# Teensy_Reactor.net
KiCad netlist of a schematic drawn in EAGLE
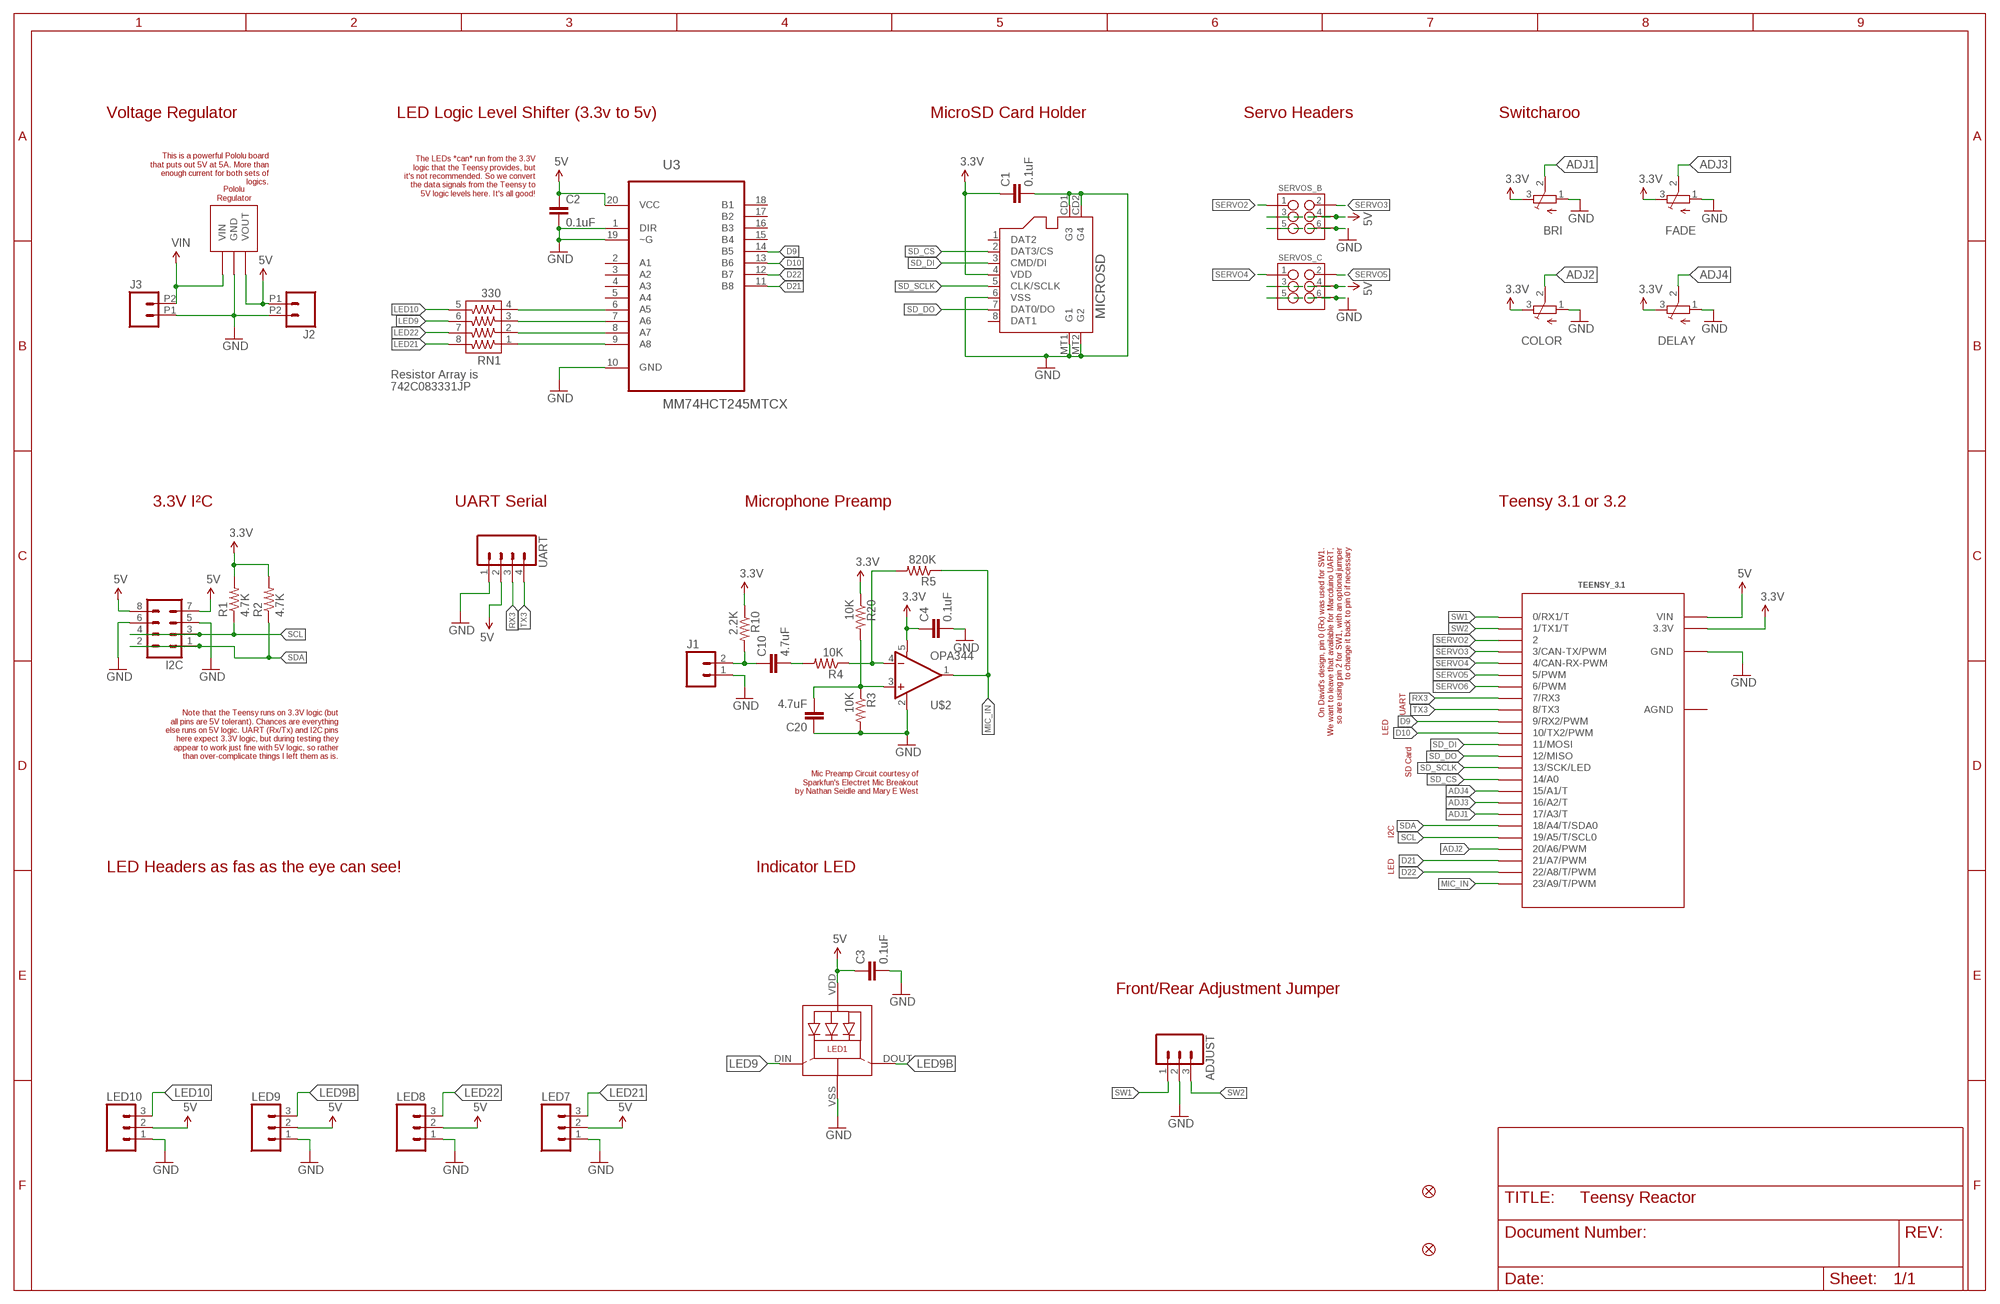
[diagram p0: schematic, sheet 1]

(export (version "E")
  (design (tool "Eeschema 10.0.6"))
  (components
    (comp (ref "ADJUST")
      (value "M03PTH")
      (footprint "eagle-import:1X03")
      (libsource (lib "eagle-import") (part "M03PTH"))
    )
    (comp (ref "BRI")
      (value "TRIMPOTEVM3V")
      (footprint "eagle-import:EVM3V")
      (libsource (lib "eagle-import") (part "TRIMPOTEVM3V"))
    )
    (comp (ref "C1")
      (value "0.1uF")
      (footprint "eagle-import:0603-CAP")
      (libsource (lib "eagle-import") (part "2.2UF-10V-20%(0603)"))
    )
    (comp (ref "C2")
      (value "0.1uF")
      (footprint "eagle-import:0603-CAP")
      (libsource (lib "eagle-import") (part "2.2UF-10V-20%(0603)"))
    )
    (comp (ref "C3")
      (value "0.1uF")
      (footprint "eagle-import:0603-CAP")
      (libsource (lib "eagle-import") (part "2.2UF-10V-20%(0603)"))
    )
    (comp (ref "C4")
      (value "0.1uF")
      (footprint "eagle-import:0603-CAP")
      (libsource (lib "eagle-import") (part "2.2UF-10V-20%(0603)"))
    )
    (comp (ref "C10")
      (value "4.7uF")
      (footprint "eagle-import:0603-CAP")
      (libsource (lib "eagle-import") (part "2.2UF-10V-20%(0603)"))
    )
    (comp (ref "C20")
      (value "4.7uF")
      (footprint "eagle-import:0603-CAP")
      (libsource (lib "eagle-import") (part "2.2UF-10V-20%(0603)"))
    )
    (comp (ref "COLOR")
      (value "TRIMPOTEVM3V")
      (footprint "eagle-import:EVM3V")
      (libsource (lib "eagle-import") (part "TRIMPOTEVM3V"))
    )
    (comp (ref "DELAY")
      (value "TRIMPOTEVM3V")
      (footprint "eagle-import:EVM3V")
      (libsource (lib "eagle-import") (part "TRIMPOTEVM3V"))
    )
    (comp (ref "FADE")
      (value "TRIMPOTEVM3V")
      (footprint "eagle-import:EVM3V")
      (libsource (lib "eagle-import") (part "TRIMPOTEVM3V"))
    )
    (comp (ref "FID1")
      (value "FIDUCIAL1X2")
      (footprint "eagle-import:FIDUCIAL-1X2")
      (libsource (lib "eagle-import") (part "FIDUCIAL1X2"))
    )
    (comp (ref "FID2")
      (value "FIDUCIAL1X2")
      (footprint "eagle-import:FIDUCIAL-1X2")
      (libsource (lib "eagle-import") (part "FIDUCIAL1X2"))
    )
    (comp (ref "I2C")
      (value "M04X2")
      (footprint "eagle-import:2X4")
      (libsource (lib "eagle-import") (part "M04X2"))
    )
    (comp (ref "J1")
      (value "M02PTH")
      (footprint "eagle-import:1X02")
      (libsource (lib "eagle-import") (part "M02PTH"))
    )
    (comp (ref "J2")
      (value "M022.54MM_SCREWTERM")
      (footprint "eagle-import:1X02_2.54_SCREWTERM")
      (libsource (lib "eagle-import") (part "M022.54MM_SCREWTERM"))
    )
    (comp (ref "J3")
      (value "M022.54MM_SCREWTERM")
      (footprint "eagle-import:1X02_2.54_SCREWTERM")
      (libsource (lib "eagle-import") (part "M022.54MM_SCREWTERM"))
    )
    (comp (ref "LED1")
      (value "WS2812BSK6812MINI")
      (footprint "eagle-import:SK6812MINI")
      (libsource (lib "eagle-import") (part "WS2812BSK6812MINI"))
    )
    (comp (ref "LED7")
      (value "M03PTH")
      (footprint "eagle-import:1X03")
      (libsource (lib "eagle-import") (part "M03PTH"))
    )
    (comp (ref "LED8")
      (value "M03PTH")
      (footprint "eagle-import:1X03")
      (libsource (lib "eagle-import") (part "M03PTH"))
    )
    (comp (ref "LED9")
      (value "M03PTH")
      (footprint "eagle-import:1X03")
      (libsource (lib "eagle-import") (part "M03PTH"))
    )
    (comp (ref "LED10")
      (value "M03PTH")
      (footprint "eagle-import:1X03")
      (libsource (lib "eagle-import") (part "M03PTH"))
    )
    (comp (ref "MICROSD")
      (value "MICROSD")
      (footprint "eagle-import:MICROSD_SMALL")
      (libsource (lib "eagle-import") (part "MICROSD"))
    )
    (comp (ref "R1")
      (value "4.7K")
      (footprint "eagle-import:0603-RES")
      (libsource (lib "eagle-import") (part "RESISTOR0603-RES"))
    )
    (comp (ref "R2")
      (value "4.7K")
      (footprint "eagle-import:0603-RES")
      (libsource (lib "eagle-import") (part "RESISTOR0603-RES"))
    )
    (comp (ref "R3")
      (value "10K")
      (footprint "eagle-import:0603-RES")
      (libsource (lib "eagle-import") (part "RESISTOR0603-RES"))
    )
    (comp (ref "R4")
      (value "10K")
      (footprint "eagle-import:0603-RES")
      (libsource (lib "eagle-import") (part "RESISTOR0603-RES"))
    )
    (comp (ref "R5")
      (value "820K")
      (footprint "eagle-import:0603-RES")
      (libsource (lib "eagle-import") (part "RESISTOR0603-RES"))
    )
    (comp (ref "R10")
      (value "2.2K")
      (footprint "eagle-import:0603-RES")
      (libsource (lib "eagle-import") (part "RESISTOR0603-RES"))
    )
    (comp (ref "R20")
      (value "10K")
      (footprint "eagle-import:0603-RES")
      (libsource (lib "eagle-import") (part "RESISTOR0603-RES"))
    )
    (comp (ref "RN1")
      (value "330")
      (footprint "eagle-import:742-8NS")
      (libsource (lib "eagle-import") (part "742-8NS"))
    )
    (comp (ref "SERVOS_B")
      (value "M03X22X3_SILK_MALE_PTH")
      (footprint "eagle-import:2X3")
      (libsource (lib "eagle-import") (part "M03X22X3_SILK_MALE_PTH"))
    )
    (comp (ref "SERVOS_C")
      (value "M03X22X3_SILK_MALE_PTH")
      (footprint "eagle-import:2X3")
      (libsource (lib "eagle-import") (part "M03X22X3_SILK_MALE_PTH"))
    )
    (comp (ref "TEENSY_3.1")
      (value "TEENSY_3.1_SOME_PINS")
      (footprint "eagle-import:TEENSY3-SOME_PINS")
      (libsource (lib "eagle-import") (part "TEENSY_3.1_SOME_PINS"))
    )
    (comp (ref "U$1")
      (value "POLOLU_REGD24V50FS_NO_HOLES")
      (footprint "eagle-import:D24V50F5_NO_HOLES")
      (libsource (lib "eagle-import") (part "POLOLU_REGD24V50FS_NO_HOLES"))
    )
    (comp (ref "U$2")
      (value "OPA344")
      (footprint "eagle-import:SOT23-5")
      (libsource (lib "eagle-import") (part "OPA344"))
    )
    (comp (ref "U3")
      (value "MM74HCT245MTCX")
      (footprint "eagle-import:SOP65P640X120-20N")
      (libsource (lib "eagle-import") (part "MM74HCT245MTCX"))
    )
    (comp (ref "UART")
      (value "M04PTH")
      (footprint "eagle-import:1X04")
      (libsource (lib "eagle-import") (part "M04PTH"))
    )
  )
  (nets
    (net (code "1") (name "/AGND") (class "Default")
      (node (ref "TEENSY_3.1") (pin "AGND") (pinfunction "AGND_AGND") (pintype "power_in"))
    )
    (net (code "2") (name "3.3V") (class "Default")
      (node (ref "BRI") (pin "3") (pinfunction "E_3") (pintype "passive"))
      (node (ref "C1") (pin "1") (pinfunction "1_1") (pintype "passive"))
      (node (ref "C4") (pin "1") (pinfunction "1_1") (pintype "passive"))
      (node (ref "COLOR") (pin "3") (pinfunction "E_3") (pintype "passive"))
      (node (ref "DELAY") (pin "3") (pinfunction "E_3") (pintype "passive"))
      (node (ref "FADE") (pin "3") (pinfunction "E_3") (pintype "passive"))
      (node (ref "MICROSD") (pin "4") (pinfunction "VDD_4") (pintype "power_in"))
      (node (ref "R1") (pin "2") (pinfunction "2_2") (pintype "passive"))
      (node (ref "R10") (pin "1") (pinfunction "1_1") (pintype "passive"))
      (node (ref "R2") (pin "2") (pinfunction "2_2") (pintype "passive"))
      (node (ref "R20") (pin "1") (pinfunction "1_1") (pintype "passive"))
      (node (ref "TEENSY_3.1") (pin "3.3V") (pinfunction "3.3V_3.3V") (pintype "power_in"))
      (node (ref "TEENSY_3.1") (pin "3.3V1") (pinfunction "3.3V_3.3V1") (pintype "power_in"))
      (node (ref "U$2") (pin "5") (pinfunction "V+_5") (pintype "power_in"))
    )
    (net (code "3") (name "5V") (class "Default")
      (node (ref "C2") (pin "1") (pinfunction "1_1") (pintype "passive"))
      (node (ref "C3") (pin "1") (pinfunction "1_1") (pintype "passive"))
      (node (ref "I2C") (pin "7") (pinfunction "7_7") (pintype "passive"))
      (node (ref "I2C") (pin "8") (pinfunction "8_8") (pintype "passive"))
      (node (ref "J2") (pin "P1") (pinfunction "1_P1") (pintype "passive"))
      (node (ref "LED1") (pin "VDD") (pinfunction "VDD_VDD") (pintype "power_in"))
      (node (ref "LED10") (pin "2") (pinfunction "2_2") (pintype "passive"))
      (node (ref "LED7") (pin "2") (pinfunction "2_2") (pintype "passive"))
      (node (ref "LED8") (pin "2") (pinfunction "2_2") (pintype "passive"))
      (node (ref "LED9") (pin "2") (pinfunction "2_2") (pintype "passive"))
      (node (ref "SERVOS_B") (pin "3") (pinfunction "3_3") (pintype "bidirectional"))
      (node (ref "SERVOS_B") (pin "4") (pinfunction "4_4") (pintype "bidirectional"))
      (node (ref "SERVOS_C") (pin "3") (pinfunction "3_3") (pintype "bidirectional"))
      (node (ref "SERVOS_C") (pin "4") (pinfunction "4_4") (pintype "bidirectional"))
      (node (ref "TEENSY_3.1") (pin "VIN") (pinfunction "VIN_VIN") (pintype "power_in"))
      (node (ref "U$1") (pin "VOUT") (pinfunction "VOUT_VOUT") (pintype "bidirectional"))
      (node (ref "U3") (pin "20") (pinfunction "VCC_20") (pintype "power_in"))
      (node (ref "UART") (pin "2") (pinfunction "2_2") (pintype "passive"))
    )
    (net (code "4") (name "ADJ1") (class "Default")
      (node (ref "BRI") (pin "2") (pinfunction "S_2") (pintype "passive"))
      (node (ref "TEENSY_3.1") (pin "17/A3") (pinfunction "17/A3/T_17/A3") (pintype "bidirectional"))
    )
    (net (code "5") (name "ADJ2") (class "Default")
      (node (ref "COLOR") (pin "2") (pinfunction "S_2") (pintype "passive"))
      (node (ref "TEENSY_3.1") (pin "20/A6") (pinfunction "20/A6/PWM_20/A6") (pintype "bidirectional"))
    )
    (net (code "6") (name "ADJ3") (class "Default")
      (node (ref "FADE") (pin "2") (pinfunction "S_2") (pintype "passive"))
      (node (ref "TEENSY_3.1") (pin "16/A2") (pinfunction "16/A2/T_16/A2") (pintype "bidirectional"))
    )
    (net (code "7") (name "ADJ4") (class "Default")
      (node (ref "DELAY") (pin "2") (pinfunction "S_2") (pintype "passive"))
      (node (ref "TEENSY_3.1") (pin "15/A1") (pinfunction "15/A1/T_15/A1") (pintype "bidirectional"))
    )
    (net (code "8") (name "D9") (class "Default")
      (node (ref "TEENSY_3.1") (pin "9") (pinfunction "9/RX2/PWM_9") (pintype "bidirectional"))
      (node (ref "U3") (pin "14") (pinfunction "B5_14") (pintype "bidirectional"))
    )
    (net (code "9") (name "D10") (class "Default")
      (node (ref "TEENSY_3.1") (pin "10") (pinfunction "10/TX2/PWM_10") (pintype "bidirectional"))
      (node (ref "U3") (pin "13") (pinfunction "B6_13") (pintype "bidirectional"))
    )
    (net (code "10") (name "D21") (class "Default")
      (node (ref "TEENSY_3.1") (pin "21/A7") (pinfunction "21/A7/PWM_21/A7") (pintype "bidirectional"))
      (node (ref "U3") (pin "11") (pinfunction "B8_11") (pintype "bidirectional"))
    )
    (net (code "11") (name "D22") (class "Default")
      (node (ref "TEENSY_3.1") (pin "22/A8") (pinfunction "22/A8/T/PWM_22/A8") (pintype "bidirectional"))
      (node (ref "U3") (pin "12") (pinfunction "B7_12") (pintype "bidirectional"))
    )
    (net (code "12") (name "GND") (class "Default")
      (node (ref "ADJUST") (pin "2") (pinfunction "2_2") (pintype "passive"))
      (node (ref "BRI") (pin "1") (pinfunction "A_1") (pintype "passive"))
      (node (ref "C1") (pin "2") (pinfunction "2_2") (pintype "passive"))
      (node (ref "C2") (pin "2") (pinfunction "2_2") (pintype "passive"))
      (node (ref "C20") (pin "1") (pinfunction "1_1") (pintype "passive"))
      (node (ref "C3") (pin "2") (pinfunction "2_2") (pintype "passive"))
      (node (ref "C4") (pin "2") (pinfunction "2_2") (pintype "passive"))
      (node (ref "COLOR") (pin "1") (pinfunction "A_1") (pintype "passive"))
      (node (ref "DELAY") (pin "1") (pinfunction "A_1") (pintype "passive"))
      (node (ref "FADE") (pin "1") (pinfunction "A_1") (pintype "passive"))
      (node (ref "I2C") (pin "5") (pinfunction "5_5") (pintype "passive"))
      (node (ref "I2C") (pin "6") (pinfunction "6_6") (pintype "passive"))
      (node (ref "J1") (pin "1") (pinfunction "1_1") (pintype "passive"))
      (node (ref "J2") (pin "P2") (pinfunction "2_P2") (pintype "passive"))
      (node (ref "J3") (pin "P1") (pinfunction "1_P1") (pintype "passive"))
      (node (ref "LED1") (pin "VSS") (pinfunction "GND_VSS") (pintype "power_in"))
      (node (ref "LED10") (pin "1") (pinfunction "1_1") (pintype "passive"))
      (node (ref "LED7") (pin "1") (pinfunction "1_1") (pintype "passive"))
      (node (ref "LED8") (pin "1") (pinfunction "1_1") (pintype "passive"))
      (node (ref "LED9") (pin "1") (pinfunction "1_1") (pintype "passive"))
      (node (ref "MICROSD") (pin "6") (pinfunction "VSS_6") (pintype "power_in"))
      (node (ref "MICROSD") (pin "CD1") (pinfunction "G3_CD1") (pintype "passive"))
      (node (ref "MICROSD") (pin "CD2") (pinfunction "G4_CD2") (pintype "passive"))
      (node (ref "MICROSD") (pin "MT1") (pinfunction "G1_MT1") (pintype "power_in"))
      (node (ref "MICROSD") (pin "MT2") (pinfunction "G2_MT2") (pintype "power_in"))
      (node (ref "R3") (pin "2") (pinfunction "2_2") (pintype "passive"))
      (node (ref "SERVOS_B") (pin "5") (pinfunction "5_5") (pintype "bidirectional"))
      (node (ref "SERVOS_B") (pin "6") (pinfunction "6_6") (pintype "bidirectional"))
      (node (ref "SERVOS_C") (pin "5") (pinfunction "5_5") (pintype "bidirectional"))
      (node (ref "SERVOS_C") (pin "6") (pinfunction "6_6") (pintype "bidirectional"))
      (node (ref "TEENSY_3.1") (pin "GND") (pinfunction "GND_GND") (pintype "power_in"))
      (node (ref "TEENSY_3.1") (pin "GND1") (pinfunction "GND_GND1") (pintype "power_in"))
      (node (ref "U$1") (pin "GND1") (pinfunction "GND_GND1") (pintype "bidirectional"))
      (node (ref "U$1") (pin "GND2") (pinfunction "GND_GND2") (pintype "bidirectional"))
      (node (ref "U$2") (pin "2") (pinfunction "V-_2") (pintype "power_in"))
      (node (ref "U3") (pin "1") (pinfunction "DIR_1") (pintype "input"))
      (node (ref "U3") (pin "10") (pinfunction "GND_10") (pintype "passive"))
      (node (ref "U3") (pin "19") (pinfunction "~{G}_19") (pintype "input"))
      (node (ref "UART") (pin "1") (pinfunction "1_1") (pintype "passive"))
    )
    (net (code "13") (name "LED9") (class "Default")
      (node (ref "LED1") (pin "DIN") (pinfunction "DI_DIN") (pintype "input"))
      (node (ref "RN1") (pin "6") (pinfunction "6_6") (pintype "passive"))
    )
    (net (code "14") (name "LED9B") (class "Default")
      (node (ref "LED1") (pin "DOUT") (pinfunction "DO_DOUT") (pintype "output"))
      (node (ref "LED9") (pin "3") (pinfunction "3_3") (pintype "passive"))
    )
    (net (code "15") (name "LED10") (class "Default")
      (node (ref "LED10") (pin "3") (pinfunction "3_3") (pintype "passive"))
      (node (ref "RN1") (pin "5") (pinfunction "5_5") (pintype "passive"))
    )
    (net (code "16") (name "LED21") (class "Default")
      (node (ref "LED7") (pin "3") (pinfunction "3_3") (pintype "passive"))
      (node (ref "RN1") (pin "8") (pinfunction "8_8") (pintype "passive"))
    )
    (net (code "17") (name "LED22") (class "Default")
      (node (ref "LED8") (pin "3") (pinfunction "3_3") (pintype "passive"))
      (node (ref "RN1") (pin "7") (pinfunction "7_7") (pintype "passive"))
    )
    (net (code "18") (name "MIC_IN") (class "Default")
      (node (ref "R5") (pin "1") (pinfunction "1_1") (pintype "passive"))
      (node (ref "TEENSY_3.1") (pin "23/A9") (pinfunction "23/A9/T/PWM_23/A9") (pintype "bidirectional"))
      (node (ref "U$2") (pin "1") (pinfunction "OUT_1") (pintype "output"))
    )
    (net (code "19") (name "Net-(C10-Pad1)") (class "Default")
      (node (ref "C10") (pin "1") (pinfunction "1_1") (pintype "passive"))
      (node (ref "J1") (pin "2") (pinfunction "2_2") (pintype "passive"))
      (node (ref "R10") (pin "2") (pinfunction "2_2") (pintype "passive"))
    )
    (net (code "20") (name "Net-(C10-Pad2)") (class "Default")
      (node (ref "C10") (pin "2") (pinfunction "2_2") (pintype "passive"))
      (node (ref "R4") (pin "2") (pinfunction "2_2") (pintype "passive"))
    )
    (net (code "21") (name "Net-(U$2-+IN)") (class "Default")
      (node (ref "C20") (pin "2") (pinfunction "2_2") (pintype "passive"))
      (node (ref "R20") (pin "2") (pinfunction "2_2") (pintype "passive"))
      (node (ref "R3") (pin "1") (pinfunction "1_1") (pintype "passive"))
      (node (ref "U$2") (pin "3") (pinfunction "+IN_3") (pintype "input"))
    )
    (net (code "22") (name "Net-(U$2--IN)") (class "Default")
      (node (ref "R4") (pin "1") (pinfunction "1_1") (pintype "passive"))
      (node (ref "R5") (pin "2") (pinfunction "2_2") (pintype "passive"))
      (node (ref "U$2") (pin "4") (pinfunction "-IN_4") (pintype "input"))
    )
    (net (code "23") (name "Net-(U3-A5)") (class "Default")
      (node (ref "RN1") (pin "4") (pinfunction "4_4") (pintype "passive"))
      (node (ref "U3") (pin "6") (pinfunction "A5_6") (pintype "bidirectional"))
    )
    (net (code "24") (name "Net-(U3-A6)") (class "Default")
      (node (ref "RN1") (pin "3") (pinfunction "3_3") (pintype "passive"))
      (node (ref "U3") (pin "7") (pinfunction "A6_7") (pintype "bidirectional"))
    )
    (net (code "25") (name "Net-(U3-A7)") (class "Default")
      (node (ref "RN1") (pin "2") (pinfunction "2_2") (pintype "passive"))
      (node (ref "U3") (pin "8") (pinfunction "A7_8") (pintype "bidirectional"))
    )
    (net (code "26") (name "Net-(U3-A8)") (class "Default")
      (node (ref "RN1") (pin "1") (pinfunction "1_1") (pintype "passive"))
      (node (ref "U3") (pin "9") (pinfunction "A8_9") (pintype "bidirectional"))
    )
    (net (code "27") (name "RX3") (class "Default")
      (node (ref "TEENSY_3.1") (pin "7") (pinfunction "7/RX3_7") (pintype "bidirectional"))
      (node (ref "UART") (pin "3") (pinfunction "3_3") (pintype "passive"))
    )
    (net (code "28") (name "SCL") (class "Default")
      (node (ref "I2C") (pin "3") (pinfunction "3_3") (pintype "passive"))
      (node (ref "I2C") (pin "4") (pinfunction "4_4") (pintype "passive"))
      (node (ref "R1") (pin "1") (pinfunction "1_1") (pintype "passive"))
      (node (ref "TEENSY_3.1") (pin "19/A5") (pinfunction "19/A5/T/SCL0_19/A5") (pintype "bidirectional"))
    )
    (net (code "29") (name "SDA") (class "Default")
      (node (ref "I2C") (pin "1") (pinfunction "1_1") (pintype "passive"))
      (node (ref "I2C") (pin "2") (pinfunction "2_2") (pintype "passive"))
      (node (ref "R2") (pin "1") (pinfunction "1_1") (pintype "passive"))
      (node (ref "TEENSY_3.1") (pin "18/A4") (pinfunction "18/A4/T/SDA0_18/A4") (pintype "bidirectional"))
    )
    (net (code "30") (name "SD_CS") (class "Default")
      (node (ref "MICROSD") (pin "2") (pinfunction "DAT3/CS_2") (pintype "input"))
      (node (ref "TEENSY_3.1") (pin "14/A0") (pinfunction "14/A0_14/A0") (pintype "bidirectional"))
    )
    (net (code "31") (name "SD_DI") (class "Default")
      (node (ref "MICROSD") (pin "3") (pinfunction "CMD/DI_3") (pintype "input"))
      (node (ref "TEENSY_3.1") (pin "11") (pinfunction "11/MOSI_11") (pintype "bidirectional"))
    )
    (net (code "32") (name "SD_DO") (class "Default")
      (node (ref "MICROSD") (pin "7") (pinfunction "DAT0/DO_7") (pintype "output"))
      (node (ref "TEENSY_3.1") (pin "12") (pinfunction "12/MISO_12") (pintype "bidirectional"))
    )
    (net (code "33") (name "SD_SCLK") (class "Default")
      (node (ref "MICROSD") (pin "5") (pinfunction "CLK/SCLK_5") (pintype "input"))
      (node (ref "TEENSY_3.1") (pin "13") (pinfunction "13/SCK/LED_13") (pintype "bidirectional"))
    )
    (net (code "34") (name "SERVO2") (class "Default")
      (node (ref "SERVOS_B") (pin "1") (pinfunction "1_1") (pintype "bidirectional"))
      (node (ref "TEENSY_3.1") (pin "2") (pinfunction "2_2") (pintype "bidirectional"))
    )
    (net (code "35") (name "SERVO3") (class "Default")
      (node (ref "SERVOS_B") (pin "2") (pinfunction "2_2") (pintype "bidirectional"))
      (node (ref "TEENSY_3.1") (pin "3") (pinfunction "3/CAN-TX/PWM_3") (pintype "bidirectional"))
    )
    (net (code "36") (name "SERVO4") (class "Default")
      (node (ref "SERVOS_C") (pin "1") (pinfunction "1_1") (pintype "bidirectional"))
      (node (ref "TEENSY_3.1") (pin "4") (pinfunction "4/CAN-RX-PWM_4") (pintype "bidirectional"))
    )
    (net (code "37") (name "SERVO5") (class "Default")
      (node (ref "SERVOS_C") (pin "2") (pinfunction "2_2") (pintype "bidirectional"))
      (node (ref "TEENSY_3.1") (pin "5") (pinfunction "5/PWM_5") (pintype "bidirectional"))
    )
    (net (code "38") (name "SERVO6") (class "Default")
      (node (ref "TEENSY_3.1") (pin "6") (pinfunction "6/PWM_6") (pintype "bidirectional"))
    )
    (net (code "39") (name "SW1") (class "Default")
      (node (ref "ADJUST") (pin "1") (pinfunction "1_1") (pintype "passive"))
      (node (ref "TEENSY_3.1") (pin "0") (pinfunction "0/RX1/T_0") (pintype "bidirectional"))
    )
    (net (code "40") (name "SW2") (class "Default")
      (node (ref "ADJUST") (pin "3") (pinfunction "3_3") (pintype "passive"))
      (node (ref "TEENSY_3.1") (pin "1") (pinfunction "1/TX1/T_1") (pintype "bidirectional"))
    )
    (net (code "41") (name "TX3") (class "Default")
      (node (ref "TEENSY_3.1") (pin "8") (pinfunction "8/TX3_8") (pintype "bidirectional"))
      (node (ref "UART") (pin "4") (pinfunction "4_4") (pintype "passive"))
    )
    (net (code "42") (name "VIN") (class "Default")
      (node (ref "J3") (pin "P2") (pinfunction "2_P2") (pintype "passive"))
      (node (ref "U$1") (pin "VIN") (pinfunction "VIN_VIN") (pintype "bidirectional"))
    )
    (net (code "43") (name "unconnected-(MICROSD-DAT1-Pad8)") (class "Default")
      (node (ref "MICROSD") (pin "8") (pinfunction "DAT1_8") (pintype "bidirectional"))
    )
    (net (code "44") (name "unconnected-(MICROSD-DAT2-Pad1)") (class "Default")
      (node (ref "MICROSD") (pin "1") (pinfunction "DAT2_1") (pintype "bidirectional"))
    )
    (net (code "45") (name "unconnected-(U3-A1-Pad2)") (class "Default")
      (node (ref "U3") (pin "2") (pinfunction "A1_2") (pintype "bidirectional"))
    )
    (net (code "46") (name "unconnected-(U3-A2-Pad3)") (class "Default")
      (node (ref "U3") (pin "3") (pinfunction "A2_3") (pintype "bidirectional"))
    )
    (net (code "47") (name "unconnected-(U3-A3-Pad4)") (class "Default")
      (node (ref "U3") (pin "4") (pinfunction "A3_4") (pintype "bidirectional"))
    )
    (net (code "48") (name "unconnected-(U3-A4-Pad5)") (class "Default")
      (node (ref "U3") (pin "5") (pinfunction "A4_5") (pintype "bidirectional"))
    )
    (net (code "49") (name "unconnected-(U3-B1-Pad18)") (class "Default")
      (node (ref "U3") (pin "18") (pinfunction "B1_18") (pintype "bidirectional"))
    )
    (net (code "50") (name "unconnected-(U3-B2-Pad17)") (class "Default")
      (node (ref "U3") (pin "17") (pinfunction "B2_17") (pintype "bidirectional"))
    )
    (net (code "51") (name "unconnected-(U3-B3-Pad16)") (class "Default")
      (node (ref "U3") (pin "16") (pinfunction "B3_16") (pintype "bidirectional"))
    )
    (net (code "52") (name "unconnected-(U3-B4-Pad15)") (class "Default")
      (node (ref "U3") (pin "15") (pinfunction "B4_15") (pintype "bidirectional"))
    )
  )
)
